# FioSaber_Prototype.net
KiCad netlist of a schematic drawn in EAGLE
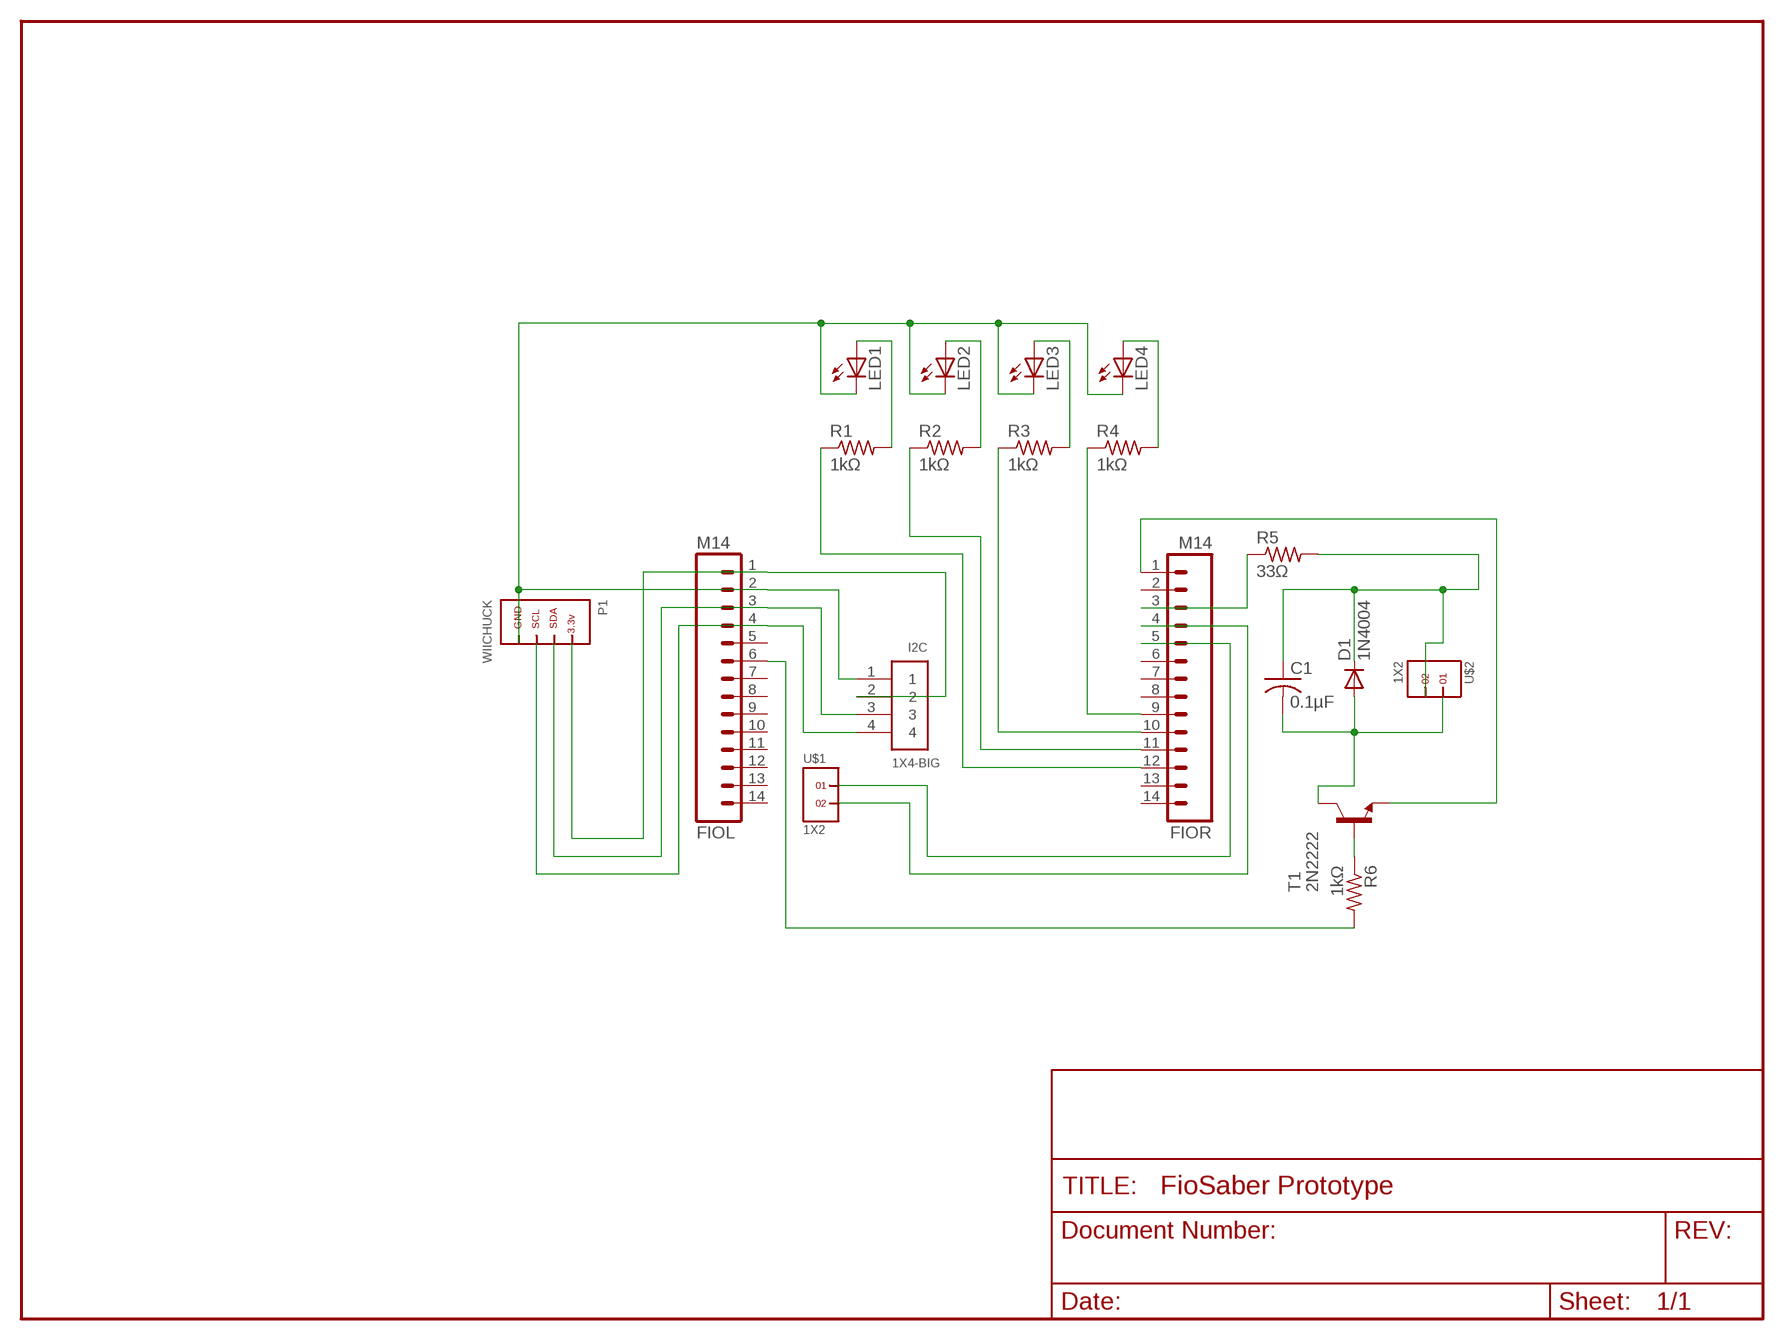
[diagram p0: schematic, sheet 1]

(export (version "E")
  (design (tool "Eeschema 10.0.6"))
  (components
    (comp (ref "C1")
      (value "0.1µF")
      (footprint "eagle-import:C025-025X050")
      (libsource (lib "eagle-import") (part "C-US025-025X050"))
    )
    (comp (ref "D1")
      (value "1N4004")
      (footprint "eagle-import:DO41-10")
      (libsource (lib "eagle-import") (part "1N4004"))
    )
    (comp (ref "FIOL")
      (value "M14")
      (footprint "eagle-import:1X14")
      (libsource (lib "eagle-import") (part "M14"))
    )
    (comp (ref "FIOR")
      (value "M14")
      (footprint "eagle-import:1X14")
      (libsource (lib "eagle-import") (part "M14"))
    )
    (comp (ref "I2C")
      (value "1X4-BIG")
      (footprint "eagle-import:1X04-BIG")
      (libsource (lib "eagle-import") (part "1X4-BIG"))
    )
    (comp (ref "LED1")
      (value "LED3MM")
      (footprint "eagle-import:LED3MM")
      (libsource (lib "eagle-import") (part "LED3MM"))
    )
    (comp (ref "LED2")
      (value "LED3MM")
      (footprint "eagle-import:LED3MM")
      (libsource (lib "eagle-import") (part "LED3MM"))
    )
    (comp (ref "LED3")
      (value "LED3MM")
      (footprint "eagle-import:LED3MM")
      (libsource (lib "eagle-import") (part "LED3MM"))
    )
    (comp (ref "LED4")
      (value "LED3MM")
      (footprint "eagle-import:LED3MM")
      (libsource (lib "eagle-import") (part "LED3MM"))
    )
    (comp (ref "P1")
      (value "WIICHUCK")
      (footprint "eagle-import:MEMOREX_RECEIVER")
      (libsource (lib "eagle-import") (part "WIICHUCK"))
    )
    (comp (ref "R1")
      (value "1kΩ")
      (footprint "eagle-import:0207_10")
      (libsource (lib "eagle-import") (part "R-US_0207/10"))
    )
    (comp (ref "R2")
      (value "1kΩ")
      (footprint "eagle-import:0207_10")
      (libsource (lib "eagle-import") (part "R-US_0207/10"))
    )
    (comp (ref "R3")
      (value "1kΩ")
      (footprint "eagle-import:0207_10")
      (libsource (lib "eagle-import") (part "R-US_0207/10"))
    )
    (comp (ref "R4")
      (value "1kΩ")
      (footprint "eagle-import:0207_10")
      (libsource (lib "eagle-import") (part "R-US_0207/10"))
    )
    (comp (ref "R5")
      (value "33Ω")
      (footprint "eagle-import:0207_10")
      (libsource (lib "eagle-import") (part "R-US_0207/10"))
    )
    (comp (ref "R6")
      (value "1kΩ")
      (footprint "eagle-import:0207_10")
      (libsource (lib "eagle-import") (part "R-US_0207/10"))
    )
    (comp (ref "T1")
      (value "2N2222")
      (footprint "eagle-import:TO92-EBC-OVAL")
      (libsource (lib "eagle-import") (part "2N2222"))
    )
    (comp (ref "U$1")
      (value "1X2")
      (footprint "eagle-import:1X2")
      (libsource (lib "eagle-import") (part "1X2"))
    )
    (comp (ref "U$2")
      (value "1X2")
      (footprint "eagle-import:1X2")
      (libsource (lib "eagle-import") (part "1X2"))
    )
  )
  (nets
    (net (code "1") (name "Net-(C1-Pad1)") (class "Default")
      (node (ref "C1") (pin "1") (pinfunction "1_1") (pintype "passive"))
      (node (ref "D1") (pin "C") (pinfunction "C_C") (pintype "passive"))
      (node (ref "R5") (pin "2") (pinfunction "2_2") (pintype "passive"))
      (node (ref "U$2") (pin "2") (pinfunction "2_2") (pintype "bidirectional"))
    )
    (net (code "2") (name "Net-(C1-Pad2)") (class "Default")
      (node (ref "C1") (pin "2") (pinfunction "2_2") (pintype "passive"))
      (node (ref "D1") (pin "A") (pinfunction "A_A") (pintype "passive"))
      (node (ref "T1") (pin "C") (pinfunction "C_C") (pintype "passive"))
      (node (ref "U$2") (pin "1") (pinfunction "1_1") (pintype "bidirectional"))
    )
    (net (code "3") (name "Net-(FIOL-Pad1)") (class "Default")
      (node (ref "FIOL") (pin "1") (pinfunction "1_1") (pintype "passive"))
      (node (ref "I2C") (pin "2") (pinfunction "2_2") (pintype "bidirectional"))
      (node (ref "P1") (pin "PWR") (pinfunction "PWR_PWR") (pintype "bidirectional"))
    )
    (net (code "4") (name "Net-(FIOL-Pad3)") (class "Default")
      (node (ref "FIOL") (pin "3") (pinfunction "3_3") (pintype "passive"))
      (node (ref "I2C") (pin "3") (pinfunction "3_3") (pintype "bidirectional"))
      (node (ref "P1") (pin "SDA") (pinfunction "SDA_SDA") (pintype "bidirectional"))
    )
    (net (code "5") (name "Net-(FIOL-Pad4)") (class "Default")
      (node (ref "FIOL") (pin "4") (pinfunction "4_4") (pintype "passive"))
      (node (ref "I2C") (pin "4") (pinfunction "4_4") (pintype "bidirectional"))
      (node (ref "P1") (pin "SCL") (pinfunction "SCL_SCL") (pintype "bidirectional"))
    )
    (net (code "6") (name "Net-(FIOL-Pad6)") (class "Default")
      (node (ref "FIOL") (pin "6") (pinfunction "6_6") (pintype "passive"))
      (node (ref "R6") (pin "2") (pinfunction "2_2") (pintype "passive"))
    )
    (net (code "7") (name "Net-(FIOR-Pad1)") (class "Default")
      (node (ref "FIOR") (pin "1") (pinfunction "1_1") (pintype "passive"))
      (node (ref "T1") (pin "E") (pinfunction "E_E") (pintype "passive"))
    )
    (net (code "8") (name "Net-(FIOR-Pad3)") (class "Default")
      (node (ref "FIOR") (pin "3") (pinfunction "3_3") (pintype "passive"))
      (node (ref "R5") (pin "1") (pinfunction "1_1") (pintype "passive"))
    )
    (net (code "9") (name "Net-(FIOR-Pad4)") (class "Default")
      (node (ref "FIOR") (pin "4") (pinfunction "4_4") (pintype "passive"))
      (node (ref "U$1") (pin "2") (pinfunction "2_2") (pintype "bidirectional"))
    )
    (net (code "10") (name "Net-(FIOR-Pad5)") (class "Default")
      (node (ref "FIOR") (pin "5") (pinfunction "5_5") (pintype "passive"))
      (node (ref "U$1") (pin "1") (pinfunction "1_1") (pintype "bidirectional"))
    )
    (net (code "11") (name "Net-(FIOR-Pad9)") (class "Default")
      (node (ref "FIOR") (pin "9") (pinfunction "9_9") (pintype "passive"))
      (node (ref "R4") (pin "1") (pinfunction "1_1") (pintype "passive"))
    )
    (net (code "12") (name "Net-(FIOR-Pad10)") (class "Default")
      (node (ref "FIOR") (pin "10") (pinfunction "10_10") (pintype "passive"))
      (node (ref "R3") (pin "1") (pinfunction "1_1") (pintype "passive"))
    )
    (net (code "13") (name "Net-(FIOR-Pad11)") (class "Default")
      (node (ref "FIOR") (pin "11") (pinfunction "11_11") (pintype "passive"))
      (node (ref "R2") (pin "1") (pinfunction "1_1") (pintype "passive"))
    )
    (net (code "14") (name "Net-(FIOR-Pad12)") (class "Default")
      (node (ref "FIOR") (pin "12") (pinfunction "12_12") (pintype "passive"))
      (node (ref "R1") (pin "1") (pinfunction "1_1") (pintype "passive"))
    )
    (net (code "15") (name "Net-(LED1-C)") (class "Default")
      (node (ref "FIOL") (pin "2") (pinfunction "2_2") (pintype "passive"))
      (node (ref "I2C") (pin "1") (pinfunction "1_1") (pintype "bidirectional"))
      (node (ref "LED1") (pin "K") (pinfunction "C_K") (pintype "passive"))
      (node (ref "LED2") (pin "K") (pinfunction "C_K") (pintype "passive"))
      (node (ref "LED3") (pin "K") (pinfunction "C_K") (pintype "passive"))
      (node (ref "LED4") (pin "K") (pinfunction "C_K") (pintype "passive"))
      (node (ref "P1") (pin "GND") (pinfunction "GND_GND") (pintype "bidirectional"))
    )
    (net (code "16") (name "Net-(LED1-PadA)") (class "Default")
      (node (ref "LED1") (pin "A") (pinfunction "A_A") (pintype "passive"))
      (node (ref "R1") (pin "2") (pinfunction "2_2") (pintype "passive"))
    )
    (net (code "17") (name "Net-(LED2-PadA)") (class "Default")
      (node (ref "LED2") (pin "A") (pinfunction "A_A") (pintype "passive"))
      (node (ref "R2") (pin "2") (pinfunction "2_2") (pintype "passive"))
    )
    (net (code "18") (name "Net-(LED3-PadA)") (class "Default")
      (node (ref "LED3") (pin "A") (pinfunction "A_A") (pintype "passive"))
      (node (ref "R3") (pin "2") (pinfunction "2_2") (pintype "passive"))
    )
    (net (code "19") (name "Net-(LED4-PadA)") (class "Default")
      (node (ref "LED4") (pin "A") (pinfunction "A_A") (pintype "passive"))
      (node (ref "R4") (pin "2") (pinfunction "2_2") (pintype "passive"))
    )
    (net (code "20") (name "Net-(R6-Pad1)") (class "Default")
      (node (ref "R6") (pin "1") (pinfunction "1_1") (pintype "passive"))
      (node (ref "T1") (pin "B") (pinfunction "B_B") (pintype "passive"))
    )
    (net (code "21") (name "unconnected-(FIOL-Pad5)") (class "Default")
      (node (ref "FIOL") (pin "5") (pinfunction "5_5") (pintype "passive"))
    )
    (net (code "22") (name "unconnected-(FIOL-Pad7)") (class "Default")
      (node (ref "FIOL") (pin "7") (pinfunction "7_7") (pintype "passive"))
    )
    (net (code "23") (name "unconnected-(FIOL-Pad8)") (class "Default")
      (node (ref "FIOL") (pin "8") (pinfunction "8_8") (pintype "passive"))
    )
    (net (code "24") (name "unconnected-(FIOL-Pad9)") (class "Default")
      (node (ref "FIOL") (pin "9") (pinfunction "9_9") (pintype "passive"))
    )
    (net (code "25") (name "unconnected-(FIOL-Pad10)") (class "Default")
      (node (ref "FIOL") (pin "10") (pinfunction "10_10") (pintype "passive"))
    )
    (net (code "26") (name "unconnected-(FIOL-Pad11)") (class "Default")
      (node (ref "FIOL") (pin "11") (pinfunction "11_11") (pintype "passive"))
    )
    (net (code "27") (name "unconnected-(FIOL-Pad12)") (class "Default")
      (node (ref "FIOL") (pin "12") (pinfunction "12_12") (pintype "passive"))
    )
    (net (code "28") (name "unconnected-(FIOL-Pad13)") (class "Default")
      (node (ref "FIOL") (pin "13") (pinfunction "13_13") (pintype "passive"))
    )
    (net (code "29") (name "unconnected-(FIOL-Pad14)") (class "Default")
      (node (ref "FIOL") (pin "14") (pinfunction "14_14") (pintype "passive"))
    )
    (net (code "30") (name "unconnected-(FIOR-Pad2)") (class "Default")
      (node (ref "FIOR") (pin "2") (pinfunction "2_2") (pintype "passive"))
    )
    (net (code "31") (name "unconnected-(FIOR-Pad6)") (class "Default")
      (node (ref "FIOR") (pin "6") (pinfunction "6_6") (pintype "passive"))
    )
    (net (code "32") (name "unconnected-(FIOR-Pad7)") (class "Default")
      (node (ref "FIOR") (pin "7") (pinfunction "7_7") (pintype "passive"))
    )
    (net (code "33") (name "unconnected-(FIOR-Pad8)") (class "Default")
      (node (ref "FIOR") (pin "8") (pinfunction "8_8") (pintype "passive"))
    )
    (net (code "34") (name "unconnected-(FIOR-Pad13)") (class "Default")
      (node (ref "FIOR") (pin "13") (pinfunction "13_13") (pintype "passive"))
    )
    (net (code "35") (name "unconnected-(FIOR-Pad14)") (class "Default")
      (node (ref "FIOR") (pin "14") (pinfunction "14_14") (pintype "passive"))
    )
  )
)
